# pavle.net
KiCad netlist of a schematic drawn in EAGLE
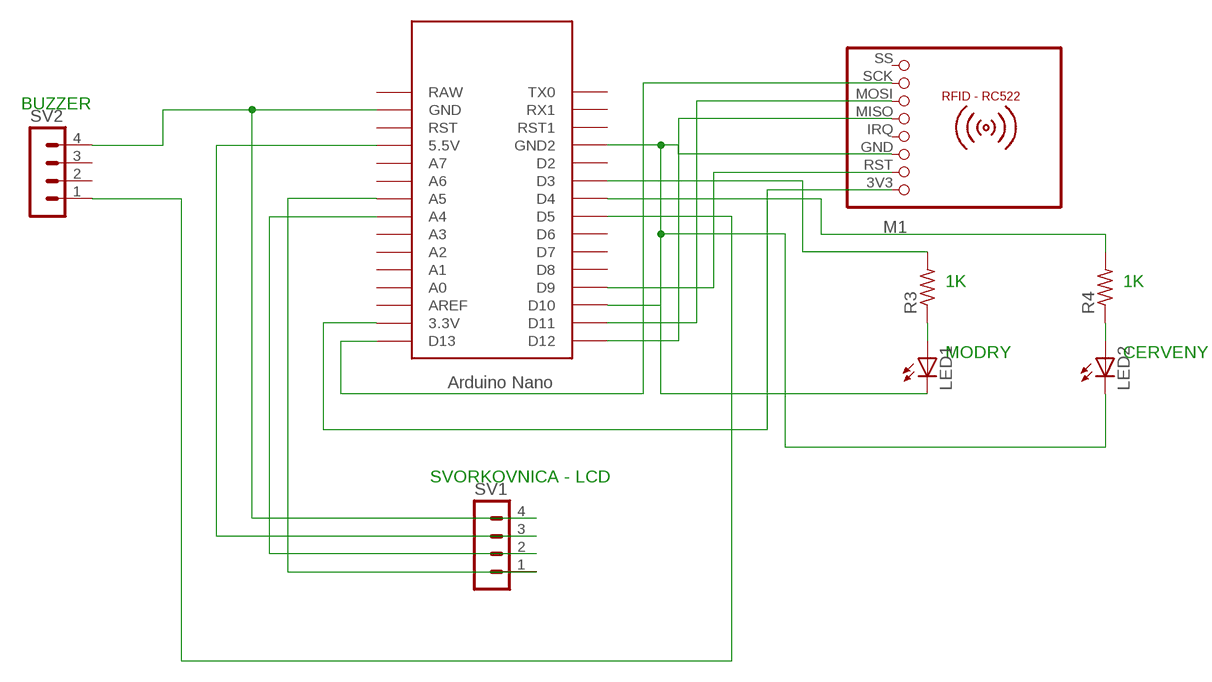
[diagram p0: schematic, sheet 1]

(export (version "E")
  (design (tool "Eeschema 10.0.6"))
  (components
    (comp (ref "LED1")
      (value "LED3MM")
      (footprint "eagle-import:LED3MM")
      (libsource (lib "eagle-import") (part "LED3MM"))
    )
    (comp (ref "LED2")
      (value "LED3MM")
      (footprint "eagle-import:LED3MM")
      (libsource (lib "eagle-import") (part "LED3MM"))
    )
    (comp (ref "M1")
      (value "RFID-RC522")
      (footprint "eagle-import:RFID-RC522")
      (libsource (lib "eagle-import") (part "RFID-RC522"))
    )
    (comp (ref "R3")
      (value "R-US_0414/5V")
      (footprint "eagle-import:0414V")
      (libsource (lib "eagle-import") (part "R-US_0414/5V"))
    )
    (comp (ref "R4")
      (value "R-US_0414/5V")
      (footprint "eagle-import:0414V")
      (libsource (lib "eagle-import") (part "R-US_0414/5V"))
    )
    (comp (ref "SV1")
      (value "MA04-1")
      (footprint "eagle-import:MA04-1")
      (libsource (lib "eagle-import") (part "MA04-1"))
    )
    (comp (ref "SV2")
      (value "MA04-1")
      (footprint "eagle-import:MA04-1")
      (libsource (lib "eagle-import") (part "MA04-1"))
    )
    (comp (ref "U$1")
      (value "NANO")
      (footprint "eagle-import:NANO")
      (libsource (lib "eagle-import") (part "NANO"))
    )
  )
  (nets
    (net (code "1") (name "Net-(LED1-C)") (class "Default")
      (node (ref "LED1") (pin "K") (pinfunction "C_K") (pintype "passive"))
      (node (ref "LED2") (pin "K") (pinfunction "C_K") (pintype "passive"))
      (node (ref "M1") (pin "GND") (pinfunction "3_GND") (pintype "passive"))
      (node (ref "U$1") (pin "GND1") (pinfunction "GND2_GND1") (pintype "bidirectional"))
    )
    (net (code "2") (name "Net-(LED1-PadA)") (class "Default")
      (node (ref "LED1") (pin "A") (pinfunction "A_A") (pintype "passive"))
      (node (ref "R3") (pin "1") (pinfunction "1_1") (pintype "passive"))
    )
    (net (code "3") (name "Net-(LED2-PadA)") (class "Default")
      (node (ref "LED2") (pin "A") (pinfunction "A_A") (pintype "passive"))
      (node (ref "R4") (pin "1") (pinfunction "1_1") (pintype "passive"))
    )
    (net (code "4") (name "Net-(M1-1)") (class "Default")
      (node (ref "M1") (pin "3V3") (pinfunction "1_3V3") (pintype "passive"))
      (node (ref "U$1") (pin "3.3V") (pinfunction "3.3V_3.3V") (pintype "bidirectional"))
    )
    (net (code "5") (name "Net-(M1-2)") (class "Default")
      (node (ref "M1") (pin "RST") (pinfunction "2_RST") (pintype "passive"))
      (node (ref "U$1") (pin "D9") (pinfunction "D9_D9") (pintype "bidirectional"))
    )
    (net (code "6") (name "Net-(M1-5)") (class "Default")
      (node (ref "M1") (pin "MISO") (pinfunction "5_MISO") (pintype "passive"))
      (node (ref "U$1") (pin "D12") (pinfunction "D12_D12") (pintype "bidirectional"))
    )
    (net (code "7") (name "Net-(M1-6)") (class "Default")
      (node (ref "M1") (pin "MOSI") (pinfunction "6_MOSI") (pintype "passive"))
      (node (ref "U$1") (pin "D11") (pinfunction "D11_D11") (pintype "bidirectional"))
    )
    (net (code "8") (name "Net-(M1-7)") (class "Default")
      (node (ref "M1") (pin "SCK") (pinfunction "7_SCK") (pintype "passive"))
      (node (ref "U$1") (pin "D13") (pinfunction "D13_D13") (pintype "bidirectional"))
    )
    (net (code "9") (name "Net-(R3-Pad2)") (class "Default")
      (node (ref "R3") (pin "2") (pinfunction "2_2") (pintype "passive"))
      (node (ref "U$1") (pin "D3") (pinfunction "D3_D3") (pintype "bidirectional"))
    )
    (net (code "10") (name "Net-(R4-Pad2)") (class "Default")
      (node (ref "R4") (pin "2") (pinfunction "2_2") (pintype "passive"))
      (node (ref "U$1") (pin "D4") (pinfunction "D4_D4") (pintype "bidirectional"))
    )
    (net (code "11") (name "Net-(SV1-Pad1)") (class "Default")
      (node (ref "SV1") (pin "1") (pinfunction "1_1") (pintype "passive"))
      (node (ref "U$1") (pin "A5") (pinfunction "A5_A5") (pintype "bidirectional"))
    )
    (net (code "12") (name "Net-(SV1-Pad2)") (class "Default")
      (node (ref "SV1") (pin "2") (pinfunction "2_2") (pintype "passive"))
      (node (ref "U$1") (pin "A4") (pinfunction "A4_A4") (pintype "bidirectional"))
    )
    (net (code "13") (name "Net-(SV1-Pad4)") (class "Default")
      (node (ref "SV1") (pin "4") (pinfunction "4_4") (pintype "passive"))
      (node (ref "SV2") (pin "4") (pinfunction "4_4") (pintype "passive"))
      (node (ref "U$1") (pin "GND") (pinfunction "GND_GND") (pintype "bidirectional"))
    )
    (net (code "14") (name "Net-(SV2-Pad1)") (class "Default")
      (node (ref "SV2") (pin "1") (pinfunction "1_1") (pintype "passive"))
      (node (ref "U$1") (pin "D5") (pinfunction "D5_D5") (pintype "bidirectional"))
    )
    (net (code "15") (name "Net-(U$1-5.5V)") (class "Default")
      (node (ref "SV1") (pin "3") (pinfunction "3_3") (pintype "passive"))
      (node (ref "U$1") (pin "5V") (pinfunction "5.5V_5V") (pintype "bidirectional"))
    )
    (net (code "16") (name "unconnected-(M1-4-PadIRQ)") (class "Default")
      (node (ref "M1") (pin "IRQ") (pinfunction "4_IRQ") (pintype "passive"))
    )
    (net (code "17") (name "unconnected-(M1-8-PadSS)") (class "Default")
      (node (ref "M1") (pin "SS") (pinfunction "8_SS") (pintype "passive"))
    )
    (net (code "18") (name "unconnected-(SV2-Pad2)") (class "Default")
      (node (ref "SV2") (pin "2") (pinfunction "2_2") (pintype "passive"))
    )
    (net (code "19") (name "unconnected-(SV2-Pad3)") (class "Default")
      (node (ref "SV2") (pin "3") (pinfunction "3_3") (pintype "passive"))
    )
    (net (code "20") (name "unconnected-(U$1-PadA0)") (class "Default")
      (node (ref "U$1") (pin "A0") (pinfunction "A0_A0") (pintype "bidirectional"))
    )
    (net (code "21") (name "unconnected-(U$1-PadA1)") (class "Default")
      (node (ref "U$1") (pin "A1") (pinfunction "A1_A1") (pintype "bidirectional"))
    )
    (net (code "22") (name "unconnected-(U$1-PadA2)") (class "Default")
      (node (ref "U$1") (pin "A2") (pinfunction "A2_A2") (pintype "bidirectional"))
    )
    (net (code "23") (name "unconnected-(U$1-PadA3)") (class "Default")
      (node (ref "U$1") (pin "A3") (pinfunction "A3_A3") (pintype "bidirectional"))
    )
    (net (code "24") (name "unconnected-(U$1-PadA6)") (class "Default")
      (node (ref "U$1") (pin "A6") (pinfunction "A6_A6") (pintype "bidirectional"))
    )
    (net (code "25") (name "unconnected-(U$1-PadA7)") (class "Default")
      (node (ref "U$1") (pin "A7") (pinfunction "A7_A7") (pintype "bidirectional"))
    )
    (net (code "26") (name "unconnected-(U$1-PadAREF)") (class "Default")
      (node (ref "U$1") (pin "AREF") (pinfunction "AREF_AREF") (pintype "bidirectional"))
    )
    (net (code "27") (name "unconnected-(U$1-PadD2)") (class "Default")
      (node (ref "U$1") (pin "D2") (pinfunction "D2_D2") (pintype "bidirectional"))
    )
    (net (code "28") (name "unconnected-(U$1-PadD6)") (class "Default")
      (node (ref "U$1") (pin "D6") (pinfunction "D6_D6") (pintype "bidirectional"))
    )
    (net (code "29") (name "unconnected-(U$1-PadD7)") (class "Default")
      (node (ref "U$1") (pin "D7") (pinfunction "D7_D7") (pintype "bidirectional"))
    )
    (net (code "30") (name "unconnected-(U$1-PadD8)") (class "Default")
      (node (ref "U$1") (pin "D8") (pinfunction "D8_D8") (pintype "bidirectional"))
    )
    (net (code "31") (name "unconnected-(U$1-PadD10)") (class "Default")
      (node (ref "U$1") (pin "D10") (pinfunction "D10_D10") (pintype "bidirectional"))
    )
    (net (code "32") (name "unconnected-(U$1-PadICSP1)") (class "Default")
      (node (ref "U$1") (pin "ICSP1") (pinfunction "ICSP1_ICSP1") (pintype "bidirectional"))
    )
    (net (code "33") (name "unconnected-(U$1-PadICSP2)") (class "Default")
      (node (ref "U$1") (pin "ICSP2") (pinfunction "ICSP2_ICSP2") (pintype "bidirectional"))
    )
    (net (code "34") (name "unconnected-(U$1-PadICSP3)") (class "Default")
      (node (ref "U$1") (pin "ICSP3") (pinfunction "ICSP3_ICSP3") (pintype "bidirectional"))
    )
    (net (code "35") (name "unconnected-(U$1-PadICSP4)") (class "Default")
      (node (ref "U$1") (pin "ICSP4") (pinfunction "ICSP4_ICSP4") (pintype "bidirectional"))
    )
    (net (code "36") (name "unconnected-(U$1-PadICSP5)") (class "Default")
      (node (ref "U$1") (pin "ICSP5") (pinfunction "ICSP5_ICSP5") (pintype "bidirectional"))
    )
    (net (code "37") (name "unconnected-(U$1-PadICSP6)") (class "Default")
      (node (ref "U$1") (pin "ICSP6") (pinfunction "ICSP6_ICSP6") (pintype "bidirectional"))
    )
    (net (code "38") (name "unconnected-(U$1-PadRAW)") (class "Default")
      (node (ref "U$1") (pin "RAW") (pinfunction "RAW_RAW") (pintype "bidirectional"))
    )
    (net (code "39") (name "unconnected-(U$1-PadRST)") (class "Default")
      (node (ref "U$1") (pin "RST") (pinfunction "RST_RST") (pintype "bidirectional"))
    )
    (net (code "40") (name "unconnected-(U$1-PadRST1)") (class "Default")
      (node (ref "U$1") (pin "RST1") (pinfunction "RST1_RST1") (pintype "bidirectional"))
    )
    (net (code "41") (name "unconnected-(U$1-PadRX1)") (class "Default")
      (node (ref "U$1") (pin "RX1") (pinfunction "RX1_RX1") (pintype "bidirectional"))
    )
    (net (code "42") (name "unconnected-(U$1-PadTX0)") (class "Default")
      (node (ref "U$1") (pin "TX0") (pinfunction "TX0_TX0") (pintype "bidirectional"))
    )
  )
)
